# CPU.net
KiCad netlist of a schematic drawn in Altium Designer
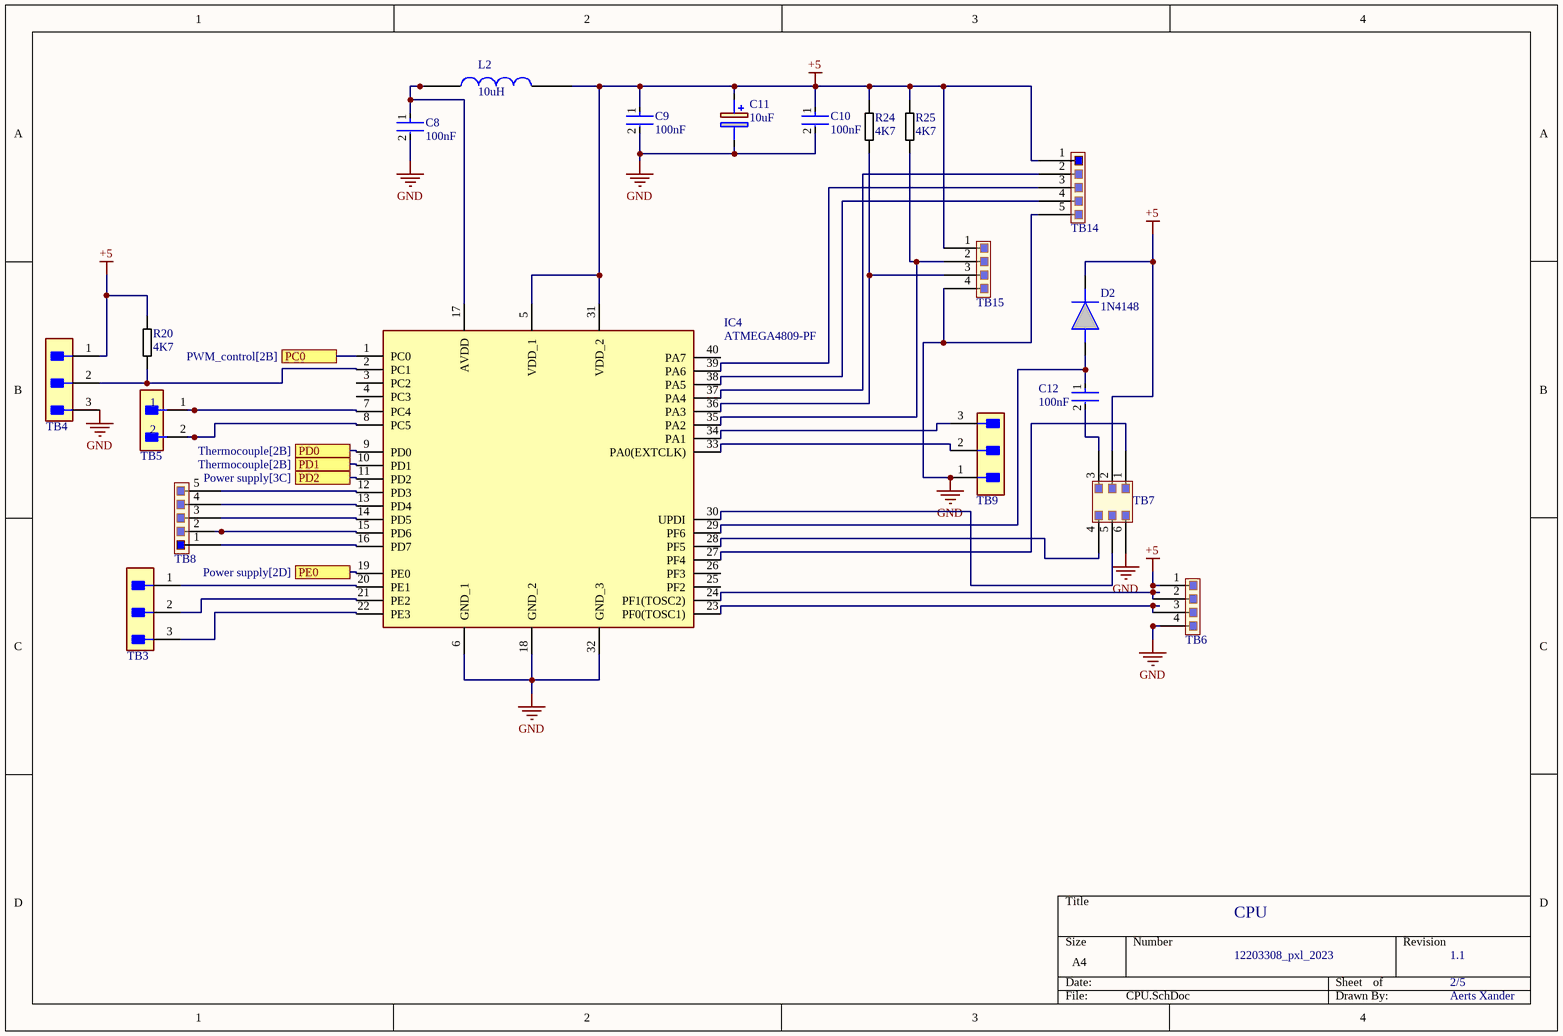
[diagram p0: CPU.SchDoc]

(export (version "E")
  (design (tool "Eeschema 10.0.6"))
  (components
    (comp (ref "C8")
      (value "100nF")
      (footprint "0805")
      (description "CAP CER 10000PF 50V X7R 0603")
      (fields (field (name "TOLERANCE") "0.1") (field (name "MANUFACTURER PART NUMBER") "CC0603KRX7R9BB103"))
      (libsource (lib "soldeerstation") (part "Capacitor 0805"))
    )
    (comp (ref "C9")
      (value "100nF")
      (footprint "0805")
      (description "CAP CER 10000PF 50V X7R 0603")
      (fields (field (name "TOLERANCE") "0.1") (field (name "MANUFACTURER PART NUMBER") "CC0603KRX7R9BB103"))
      (libsource (lib "soldeerstation") (part "Capacitor 0805"))
    )
    (comp (ref "C10")
      (value "100nF")
      (footprint "0805")
      (description "CAP CER 10000PF 50V X7R 0603")
      (fields (field (name "TOLERANCE") "0.1") (field (name "MANUFACTURER PART NUMBER") "CC0603KRX7R9BB103"))
      (libsource (lib "soldeerstation") (part "Capacitor 0805"))
    )
    (comp (ref "C11")
      (value "10uF")
      (footprint "10uF tht")
      (libsource (lib "soldeerstation") (part "10uF tht"))
    )
    (comp (ref "C12")
      (value "100nF")
      (footprint "0805")
      (description "CAP CER 10000PF 50V X7R 0603")
      (fields (field (name "TOLERANCE") "0.1") (field (name "MANUFACTURER PART NUMBER") "CC0603KRX7R9BB103"))
      (libsource (lib "soldeerstation") (part "Capacitor 0805"))
    )
    (comp (ref "D2")
      (value "1N4148")
      (footprint "1n4148")
      (description "Small Signal Diode, 100V 0.3A 2-Pin DO35")
      (fields (field (name "MOUSER PART NUMBER") "512-1N4148"))
      (libsource (lib "soldeerstation") (part "1N4148"))
    )
    (comp (ref "IC4")
      (value "ATMEGA4809-PF")
      (footprint "ATMEGA4809-PF")
      (description "Integrated Circuit")
      (fields (field (name "MOUSER PART NUMBER") "556-ATMEGA4809-PF"))
      (libsource (lib "soldeerstation") (part "ATMEGA4809-PF"))
    )
    (comp (ref "L2")
      (value "10uH")
      (footprint "10uH tht")
      (libsource (lib "soldeerstation") (part "10uH tht"))
    )
    (comp (ref "R20")
      (value "4K7")
      (footprint "0805")
      (fields (field (name "MANUFACTURER") "Vishay Dale") (field (name "PART NUMBER") "CRCW08050000Z0EA"))
      (libsource (lib "soldeerstation") (part "resistor"))
    )
    (comp (ref "R24")
      (value "4K7")
      (footprint "0805")
      (fields (field (name "MANUFACTURER") "Vishay Dale") (field (name "PART NUMBER") "CRCW08050000Z0EA"))
      (libsource (lib "soldeerstation") (part "resistor"))
    )
    (comp (ref "R25")
      (value "4K7")
      (footprint "0805")
      (fields (field (name "MANUFACTURER") "Vishay Dale") (field (name "PART NUMBER") "CRCW08050000Z0EA"))
      (libsource (lib "soldeerstation") (part "resistor"))
    )
    (comp (ref "TB3")
      (value "87224-3")
      (footprint "3x1 header tht")
      (description "CONN HEADER VERT 3POS 2.54MM")
      (libsource (lib "soldeerstation") (part "3x1 header tht"))
    )
    (comp (ref "TB4")
      (value "87224-3")
      (footprint "3x1 header tht")
      (description "CONN HEADER VERT 3POS 2.54MM")
      (libsource (lib "soldeerstation") (part "3x1 header tht"))
    )
    (comp (ref "TB5")
      (value "TSW-102-07-L-S")
      (footprint "2x1 header tht")
      (description "CONN HEADER VERT 2POS 2.54MM")
      (libsource (lib "soldeerstation") (part "2x1 header tht"))
    )
    (comp (ref "TB6")
      (value "4x1 header tht")
      (footprint "4x1 header tht")
      (libsource (lib "soldeerstation") (part "4x1 header tht"))
    )
    (comp (ref "TB7")
      (value "6x2 header tht")
      (footprint "6x2 header tht")
      (libsource (lib "soldeerstation") (part "6x2 header tht"))
    )
    (comp (ref "TB8")
      (value "5x1 header tht")
      (footprint "5x1 header tht")
      (libsource (lib "soldeerstation") (part "5x1 header tht"))
    )
    (comp (ref "TB9")
      (value "87224-3")
      (footprint "3x1 header tht")
      (description "CONN HEADER VERT 3POS 2.54MM")
      (libsource (lib "") (part "3x1 header tht_1"))
    )
    (comp (ref "TB14")
      (value "5x1 header tht")
      (footprint "5x1 header tht")
      (libsource (lib "") (part "5x1 header tht_1"))
    )
    (comp (ref "TB15")
      (value "4x1 header tht")
      (footprint "4x1 header tht")
      (libsource (lib "soldeerstation") (part "4x1 header tht"))
    )
  )
  (nets
    (net (code "1") (name "+5") (class "Default")
      (node (ref "C10") (pin "1") (pinfunction "1_1") (pintype "passive"))
      (node (ref "C11") (pin "1") (pinfunction "+_1") (pintype "passive"))
      (node (ref "C9") (pin "1") (pinfunction "1_1") (pintype "passive"))
      (node (ref "D2") (pin "1") (pinfunction "K_1") (pintype "passive"))
      (node (ref "IC4") (pin "31") (pinfunction "VDD_2_31") (pintype "passive"))
      (node (ref "IC4") (pin "5") (pinfunction "VDD_1_5") (pintype "passive"))
      (node (ref "L2") (pin "2") (pinfunction "32_2") (pintype "passive"))
      (node (ref "R20") (pin "2") (pinfunction "2_2") (pintype "passive"))
      (node (ref "R24") (pin "2") (pinfunction "2_2") (pintype "passive"))
      (node (ref "R25") (pin "2") (pinfunction "2_2") (pintype "passive"))
      (node (ref "TB14") (pin "1") (pinfunction "20_1") (pintype "passive"))
      (node (ref "TB15") (pin "1") (pinfunction "16_1") (pintype "passive"))
      (node (ref "TB4") (pin "1") (pinfunction "1_1") (pintype "passive"))
      (node (ref "TB6") (pin "1") (pinfunction "16_1") (pintype "passive"))
      (node (ref "TB7") (pin "2") (pinfunction "22_2") (pintype "passive"))
    )
    (net (code "2") (name "/PC0") (class "Default")
      (node (ref "IC4") (pin "1") (pinfunction "PC0_1") (pintype "passive"))
    )
    (net (code "3") (name "/PD0") (class "Default")
      (node (ref "IC4") (pin "9") (pinfunction "PD0_9") (pintype "passive"))
    )
    (net (code "4") (name "/PD1") (class "Default")
      (node (ref "IC4") (pin "10") (pinfunction "PD1_10") (pintype "passive"))
    )
    (net (code "5") (name "/PD2") (class "Default")
      (node (ref "IC4") (pin "11") (pinfunction "PD2_11") (pintype "passive"))
    )
    (net (code "6") (name "/PE0") (class "Default")
      (node (ref "IC4") (pin "19") (pinfunction "PE0_19") (pintype "passive"))
    )
    (net (code "7") (name "GND") (class "Default")
      (node (ref "C10") (pin "2") (pinfunction "2_2") (pintype "passive"))
      (node (ref "C11") (pin "2") (pinfunction "-_2") (pintype "passive"))
      (node (ref "C8") (pin "2") (pinfunction "2_2") (pintype "passive"))
      (node (ref "C9") (pin "2") (pinfunction "2_2") (pintype "passive"))
      (node (ref "IC4") (pin "18") (pinfunction "GND_2_18") (pintype "passive"))
      (node (ref "IC4") (pin "32") (pinfunction "GND_3_32") (pintype "passive"))
      (node (ref "IC4") (pin "6") (pinfunction "GND_1_6") (pintype "passive"))
      (node (ref "TB14") (pin "5") (pinfunction "19_5") (pintype "passive"))
      (node (ref "TB15") (pin "4") (pinfunction "19_4") (pintype "passive"))
      (node (ref "TB4") (pin "3") (pinfunction "3_3") (pintype "passive"))
      (node (ref "TB6") (pin "4") (pinfunction "19_4") (pintype "passive"))
      (node (ref "TB7") (pin "6") (pinfunction "24_6") (pintype "passive"))
      (node (ref "TB9") (pin "1") (pinfunction "1_1") (pintype "passive"))
    )
    (net (code "8") (name "Net-(D2-A)") (class "Default")
      (node (ref "C12") (pin "1") (pinfunction "1_1") (pintype "passive"))
      (node (ref "D2") (pin "2") (pinfunction "A_2") (pintype "passive"))
      (node (ref "IC4") (pin "29") (pinfunction "PF6_29") (pintype "passive"))
    )
    (net (code "9") (name "Net-(IC4-AVDD)") (class "Default")
      (node (ref "C8") (pin "1") (pinfunction "1_1") (pintype "passive"))
      (node (ref "IC4") (pin "17") (pinfunction "AVDD_17") (pintype "passive"))
      (node (ref "L2") (pin "1") (pinfunction "31_1") (pintype "passive"))
    )
    (net (code "10") (name "Net-(IC4-PA0(EXTCLK))") (class "Default")
      (node (ref "IC4") (pin "33") (pinfunction "PA0(EXTCLK)_33") (pintype "passive"))
      (node (ref "TB9") (pin "2") (pinfunction "2_2") (pintype "passive"))
    )
    (net (code "11") (name "Net-(IC4-PA1)") (class "Default")
      (node (ref "IC4") (pin "34") (pinfunction "PA1_34") (pintype "passive"))
      (node (ref "TB9") (pin "3") (pinfunction "3_3") (pintype "passive"))
    )
    (net (code "12") (name "Net-(IC4-PA2)") (class "Default")
      (node (ref "IC4") (pin "35") (pinfunction "PA2_35") (pintype "passive"))
      (node (ref "R25") (pin "1") (pinfunction "1_1") (pintype "passive"))
      (node (ref "TB15") (pin "2") (pinfunction "17_2") (pintype "passive"))
    )
    (net (code "13") (name "Net-(IC4-PA3)") (class "Default")
      (node (ref "IC4") (pin "36") (pinfunction "PA3_36") (pintype "passive"))
      (node (ref "R24") (pin "1") (pinfunction "1_1") (pintype "passive"))
      (node (ref "TB15") (pin "3") (pinfunction "18_3") (pintype "passive"))
    )
    (net (code "14") (name "Net-(IC4-PA4)") (class "Default")
      (node (ref "IC4") (pin "37") (pinfunction "PA4_37") (pintype "passive"))
      (node (ref "TB14") (pin "2") (pinfunction "16_2") (pintype "passive"))
    )
    (net (code "15") (name "Net-(IC4-PA5)") (class "Default")
      (node (ref "IC4") (pin "38") (pinfunction "PA5_38") (pintype "passive"))
      (node (ref "TB14") (pin "4") (pinfunction "18_4") (pintype "passive"))
    )
    (net (code "16") (name "Net-(IC4-PA6)") (class "Default")
      (node (ref "IC4") (pin "39") (pinfunction "PA6_39") (pintype "passive"))
      (node (ref "TB14") (pin "3") (pinfunction "17_3") (pintype "passive"))
    )
    (net (code "17") (name "Net-(IC4-PC1)") (class "Default")
      (node (ref "IC4") (pin "2") (pinfunction "PC1_2") (pintype "passive"))
      (node (ref "R20") (pin "1") (pinfunction "1_1") (pintype "passive"))
      (node (ref "TB4") (pin "2") (pinfunction "2_2") (pintype "passive"))
    )
    (net (code "18") (name "Net-(IC4-PC4)") (class "Default")
      (node (ref "IC4") (pin "7") (pinfunction "PC4_7") (pintype "passive"))
      (node (ref "TB5") (pin "1") (pinfunction "1_1") (pintype "passive"))
    )
    (net (code "19") (name "Net-(IC4-PC5)") (class "Default")
      (node (ref "IC4") (pin "8") (pinfunction "PC5_8") (pintype "passive"))
      (node (ref "TB5") (pin "2") (pinfunction "2_2") (pintype "passive"))
    )
    (net (code "20") (name "Net-(IC4-PD3)") (class "Default")
      (node (ref "IC4") (pin "12") (pinfunction "PD3_12") (pintype "passive"))
      (node (ref "TB8") (pin "5") (pinfunction "19_5") (pintype "passive"))
    )
    (net (code "21") (name "Net-(IC4-PD4)") (class "Default")
      (node (ref "IC4") (pin "13") (pinfunction "PD4_13") (pintype "passive"))
      (node (ref "TB8") (pin "4") (pinfunction "18_4") (pintype "passive"))
    )
    (net (code "22") (name "Net-(IC4-PD5)") (class "Default")
      (node (ref "IC4") (pin "14") (pinfunction "PD5_14") (pintype "passive"))
      (node (ref "TB8") (pin "3") (pinfunction "17_3") (pintype "passive"))
    )
    (net (code "23") (name "Net-(IC4-PD6)") (class "Default")
      (node (ref "IC4") (pin "15") (pinfunction "PD6_15") (pintype "passive"))
      (node (ref "TB8") (pin "2") (pinfunction "16_2") (pintype "passive"))
    )
    (net (code "24") (name "Net-(IC4-PD7)") (class "Default")
      (node (ref "IC4") (pin "16") (pinfunction "PD7_16") (pintype "passive"))
      (node (ref "TB8") (pin "1") (pinfunction "20_1") (pintype "passive"))
    )
    (net (code "25") (name "Net-(IC4-PE1)") (class "Default")
      (node (ref "IC4") (pin "20") (pinfunction "PE1_20") (pintype "passive"))
      (node (ref "TB3") (pin "1") (pinfunction "1_1") (pintype "passive"))
    )
    (net (code "26") (name "Net-(IC4-PE2)") (class "Default")
      (node (ref "IC4") (pin "21") (pinfunction "PE2_21") (pintype "passive"))
      (node (ref "TB3") (pin "2") (pinfunction "2_2") (pintype "passive"))
    )
    (net (code "27") (name "Net-(IC4-PE3)") (class "Default")
      (node (ref "IC4") (pin "22") (pinfunction "PE3_22") (pintype "passive"))
      (node (ref "TB3") (pin "3") (pinfunction "3_3") (pintype "passive"))
    )
    (net (code "28") (name "Net-(IC4-PF0(TOSC1))") (class "Default")
      (node (ref "IC4") (pin "23") (pinfunction "PF0(TOSC1)_23") (pintype "passive"))
      (node (ref "TB6") (pin "3") (pinfunction "18_3") (pintype "passive"))
    )
    (net (code "29") (name "Net-(IC4-PF1(TOSC2))") (class "Default")
      (node (ref "IC4") (pin "24") (pinfunction "PF1(TOSC2)_24") (pintype "passive"))
      (node (ref "TB6") (pin "2") (pinfunction "17_2") (pintype "passive"))
    )
    (net (code "30") (name "Net-(IC4-PF4)") (class "Default")
      (node (ref "IC4") (pin "27") (pinfunction "PF4_27") (pintype "passive"))
      (node (ref "TB7") (pin "1") (pinfunction "21_1") (pintype "passive"))
    )
    (net (code "31") (name "Net-(IC4-PF5)") (class "Default")
      (node (ref "IC4") (pin "28") (pinfunction "PF5_28") (pintype "passive"))
      (node (ref "TB7") (pin "4") (pinfunction "26_4") (pintype "passive"))
    )
    (net (code "32") (name "Net-(IC4-UPDI)") (class "Default")
      (node (ref "IC4") (pin "30") (pinfunction "UPDI_30") (pintype "passive"))
      (node (ref "TB7") (pin "5") (pinfunction "25_5") (pintype "passive"))
    )
    (net (code "33") (name "Net-(TB7-23)") (class "Default")
      (node (ref "C12") (pin "2") (pinfunction "2_2") (pintype "passive"))
      (node (ref "TB7") (pin "3") (pinfunction "23_3") (pintype "passive"))
    )
    (net (code "34") (name "unconnected-(IC4-PA7-Pad40)") (class "Default")
      (node (ref "IC4") (pin "40") (pinfunction "PA7_40") (pintype "passive"))
    )
    (net (code "35") (name "unconnected-(IC4-PC2-Pad3)") (class "Default")
      (node (ref "IC4") (pin "3") (pinfunction "PC2_3") (pintype "passive"))
    )
    (net (code "36") (name "unconnected-(IC4-PC3-Pad4)") (class "Default")
      (node (ref "IC4") (pin "4") (pinfunction "PC3_4") (pintype "passive"))
    )
    (net (code "37") (name "unconnected-(IC4-PF2-Pad25)") (class "Default")
      (node (ref "IC4") (pin "25") (pinfunction "PF2_25") (pintype "passive"))
    )
    (net (code "38") (name "unconnected-(IC4-PF3-Pad26)") (class "Default")
      (node (ref "IC4") (pin "26") (pinfunction "PF3_26") (pintype "passive"))
    )
  )
)
